# pwm_buffers_fault_sig.net
KiCad netlist of a schematic drawn in Altium Designer
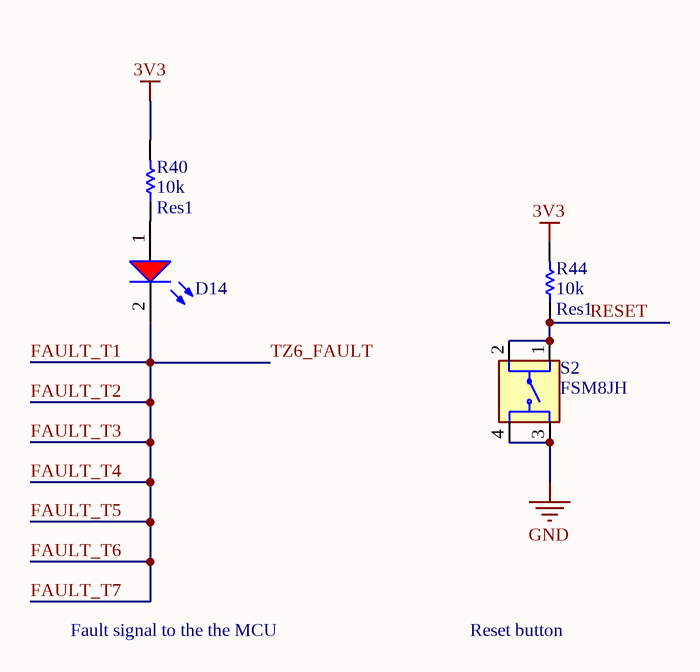
[diagram p0: pwm_buffers_fault_sig.SchDoc]

(export (version "E")
  (design (tool "Eeschema 10.0.6"))
  (components
    (comp (ref "D14")
      (value "Super Red, 2V, 40°")
      (footprint "WL-TMRC_D3.95H5.3")
      (description "WL-TMRC Mono-color Round Color, THT, D3.95 x H5.3mm, Super Red, 2V, 40°")
      (fields
        (field (name "MANUFACTURER PART NUMBER") "151031SS04000")
        (field (name "MANUFACTURER") "Wurth Elektronik")
      )
      (libsource (lib "Altium_LED_WL-TMRC") (part "151031SS04000"))
    )
    (comp (ref "R40")
      (value "Res1")
      (footprint "AXIAL-0.4")
      (description "Resistor")
      (fields (field (name "ALTIUM_VALUE") "10k") (field (name "PUBLISHER") "Altium Limited"))
      (libsource (lib "Miscellaneous Devices") (part "Res1"))
    )
    (comp (ref "R44")
      (value "Res1")
      (footprint "AXIAL-0.4")
      (description "Resistor")
      (fields (field (name "ALTIUM_VALUE") "10k") (field (name "PUBLISHER") "Altium Limited"))
      (libsource (lib "Miscellaneous Devices") (part "Res1"))
    )
    (comp (ref "S2")
      (value "FSM8JH")
      (footprint "SW_FSM8JH")
      (description "Tactile Switch SPST-NO Top Actuated Through Hole")
      (fields (field (name "MF") "TE Connectivity"))
      (libsource (lib "FSM8JH_tactile") (part "FSM8JH"))
    )
  )
  (nets
    (net (code "1") (name "/FAULT_T1") (class "Default")
      (node (ref "D14") (pin "2") (pinfunction "K_2") (pintype "passive"))
    )
    (net (code "2") (name "/RESET") (class "Default")
      (node (ref "R44") (pin "1") (pinfunction "1_1") (pintype "passive"))
      (node (ref "S2") (pin "1") (pinfunction "1_1") (pintype "passive"))
      (node (ref "S2") (pin "2") (pinfunction "2_2") (pintype "passive"))
    )
    (net (code "3") (name "3V3") (class "Default")
      (node (ref "R40") (pin "2") (pinfunction "2_2") (pintype "passive"))
      (node (ref "R44") (pin "2") (pinfunction "2_2") (pintype "passive"))
    )
    (net (code "4") (name "GND") (class "Default")
      (node (ref "S2") (pin "3") (pinfunction "3_3") (pintype "passive"))
      (node (ref "S2") (pin "4") (pinfunction "4_4") (pintype "passive"))
    )
    (net (code "5") (name "Net-(D14-A)") (class "Default")
      (node (ref "D14") (pin "1") (pinfunction "A_1") (pintype "passive"))
      (node (ref "R40") (pin "1") (pinfunction "1_1") (pintype "passive"))
    )
  )
)
